# design.net
KiCad netlist of a schematic drawn in Altium Designer
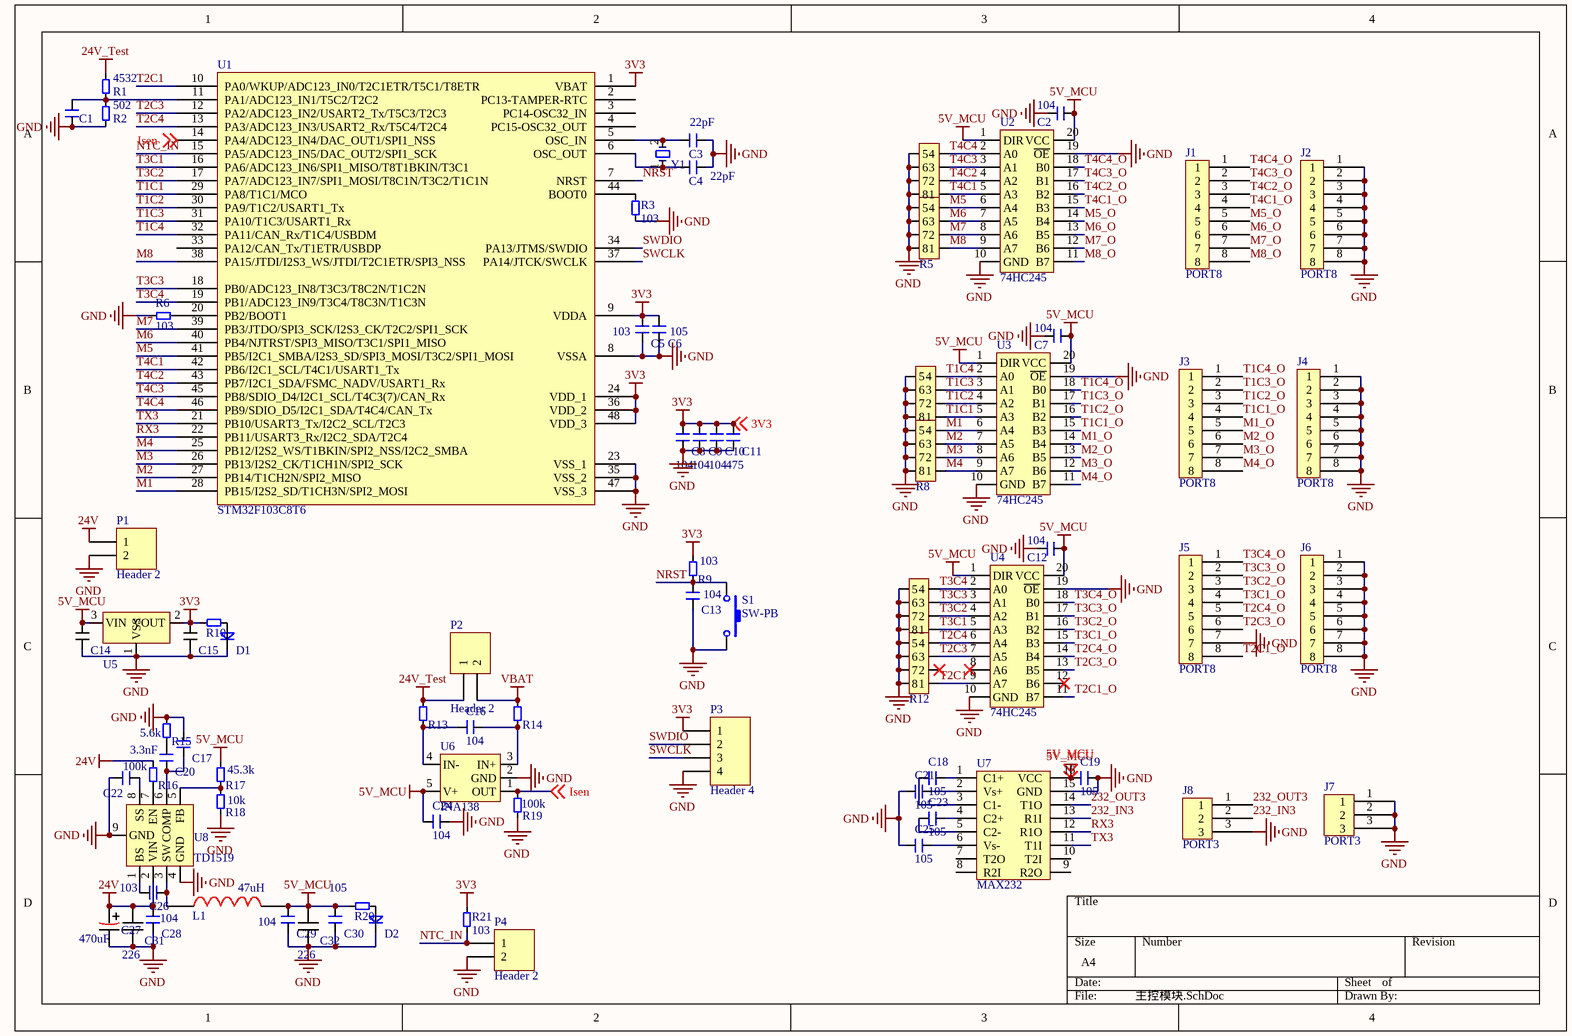
[diagram p0: 主控模块.SchDoc]

(export (version "E")
  (design (tool "Eeschema 10.0.6"))
  (components
    (comp (ref "C1") (value "0603C") (footprint "0603C") (libsource (lib "水下机器人电调控制板2020") (part "0603C")))
    (comp (ref "C2")
      (value "0603C")
      (footprint "0603C")
      (fields (field (name "PARAMETER 1") "104"))
      (libsource (lib "水下机器人电调控制板2020") (part "0603C"))
    )
    (comp (ref "C3")
      (value "0603C")
      (footprint "0603C")
      (fields (field (name "PARAMETER 1") "22pF"))
      (libsource (lib "水下机器人电调控制板2020") (part "0603C"))
    )
    (comp (ref "C4")
      (value "0603C")
      (footprint "0603C")
      (fields (field (name "PARAMETER 1") "22pF"))
      (libsource (lib "水下机器人电调控制板2020") (part "0603C"))
    )
    (comp (ref "C5")
      (value "0603C")
      (footprint "0603C")
      (fields (field (name "PARAMETER 1") "103"))
      (libsource (lib "水下机器人电调控制板2020") (part "0603C"))
    )
    (comp (ref "C6")
      (value "0603C")
      (footprint "0603C")
      (fields (field (name "PARAMETER 1") "105"))
      (libsource (lib "水下机器人电调控制板2020") (part "0603C"))
    )
    (comp (ref "C7")
      (value "0603C")
      (footprint "0603C")
      (fields (field (name "PARAMETER 1") "104"))
      (libsource (lib "水下机器人电调控制板2020") (part "0603C"))
    )
    (comp (ref "C8")
      (value "0603C")
      (footprint "0603C")
      (fields (field (name "PARAMETER 1") "104"))
      (libsource (lib "水下机器人电调控制板2020") (part "0603C"))
    )
    (comp (ref "C9")
      (value "0603C")
      (footprint "0603C")
      (fields (field (name "PARAMETER 1") "104"))
      (libsource (lib "水下机器人电调控制板2020") (part "0603C"))
    )
    (comp (ref "C10")
      (value "0603C")
      (footprint "0603C")
      (fields (field (name "PARAMETER 1") "104"))
      (libsource (lib "水下机器人电调控制板2020") (part "0603C"))
    )
    (comp (ref "C11")
      (value "0603C")
      (footprint "0603C")
      (fields (field (name "PARAMETER 1") "475"))
      (libsource (lib "水下机器人电调控制板2020") (part "0603C"))
    )
    (comp (ref "C12")
      (value "0603C")
      (footprint "0603C")
      (fields (field (name "PARAMETER 1") "104"))
      (libsource (lib "水下机器人电调控制板2020") (part "0603C"))
    )
    (comp (ref "C13")
      (value "0603C")
      (footprint "0603C")
      (fields (field (name "PARAMETER 1") "104"))
      (libsource (lib "水下机器人电调控制板2020") (part "0603C"))
    )
    (comp (ref "C14") (value "0805C") (footprint "0805C") (libsource (lib "水下去机器人控制板2020") (part "0805C")))
    (comp (ref "C15") (value "0805C") (footprint "0805C") (libsource (lib "水下去机器人控制板2020") (part "0805C")))
    (comp (ref "C16")
      (value "0603C")
      (footprint "0603C")
      (fields (field (name "PARAMETER 1") "104"))
      (libsource (lib "水下去机器人控制板2020") (part "0603C"))
    )
    (comp (ref "C17") (value "0603C") (footprint "0603C") (libsource (lib "水下去机器人控制板2020") (part "0603C")))
    (comp (ref "C18")
      (value "0603C")
      (footprint "0603C")
      (fields (field (name "PARAMETER 1") "105"))
      (libsource (lib "水下去机器人控制板2020") (part "0603C"))
    )
    (comp (ref "C19")
      (value "0603C")
      (footprint "0603C")
      (fields (field (name "PARAMETER 1") "105"))
      (libsource (lib "水下去机器人控制板2020") (part "0603C"))
    )
    (comp (ref "C20")
      (value "0603C")
      (footprint "0603C")
      (fields (field (name "PARAMETER 1") "3.3nF"))
      (libsource (lib "水下去机器人控制板2020") (part "0603C"))
    )
    (comp (ref "C21")
      (value "0603C")
      (footprint "0603C")
      (fields (field (name "PARAMETER 1") "105"))
      (libsource (lib "水下去机器人控制板2020") (part "0603C"))
    )
    (comp (ref "C22") (value "0603C") (footprint "0603C") (libsource (lib "水下去机器人控制板2020") (part "0603C")))
    (comp (ref "C23")
      (value "0603C")
      (footprint "0603C")
      (fields (field (name "PARAMETER 1") "105"))
      (libsource (lib "水下去机器人控制板2020") (part "0603C"))
    )
    (comp (ref "C24")
      (value "0603C")
      (footprint "0603C")
      (fields (field (name "PARAMETER 1") "104"))
      (libsource (lib "水下去机器人控制板2020") (part "0603C"))
    )
    (comp (ref "C25")
      (value "0603C")
      (footprint "0603C")
      (fields (field (name "PARAMETER 1") "105"))
      (libsource (lib "水下去机器人控制板2020") (part "0603C"))
    )
    (comp (ref "C26")
      (value "0603C")
      (footprint "0603C")
      (fields (field (name "PARAMETER 1") "103"))
      (libsource (lib "水下去机器人控制板2020") (part "0603C"))
    )
    (comp (ref "C27")
      (value "10*10贴片电解电容")
      (footprint "CAP-10*10.2")
      (fields (field (name "PARAMETER 1") "470uF"))
      (libsource (lib "水下去机器人控制板2020") (part "10*10贴片电解电容"))
    )
    (comp (ref "C28")
      (value "0603C")
      (footprint "0603C")
      (fields (field (name "PARAMETER 1") "104"))
      (libsource (lib "水下去机器人控制板2020") (part "0603C"))
    )
    (comp (ref "C29")
      (value "0603C")
      (footprint "0603C")
      (fields (field (name "PARAMETER 1") "104"))
      (libsource (lib "水下去机器人控制板2020") (part "0603C"))
    )
    (comp (ref "C30")
      (value "0603C")
      (footprint "0603C")
      (fields (field (name "PARAMETER 1") "105"))
      (libsource (lib "水下去机器人控制板2020") (part "0603C"))
    )
    (comp (ref "C31")
      (value "1206C")
      (footprint "1206C")
      (fields (field (name "PARAMETER 1") "226"))
      (libsource (lib "") (part "1206C_1"))
    )
    (comp (ref "C32")
      (value "1206C")
      (footprint "固态电容5*9")
      (fields (field (name "PARAMETER 1") "226"))
      (libsource (lib "水下去机器人控制板2020") (part "1206C"))
    )
    (comp (ref "D1") (value "0603D") (footprint "0603D") (libsource (lib "水下去机器人控制板2020") (part "0603D")))
    (comp (ref "D2") (value "0603D") (footprint "0603D") (libsource (lib "水下去机器人控制板2020") (part "0603D")))
    (comp (ref "J1") (value "PORT8") (footprint "PORT8") (libsource (lib "水下机器人电调控制板2020") (part "PORT8")))
    (comp (ref "J2") (value "PORT8") (footprint "PORT8") (libsource (lib "水下机器人电调控制板2020") (part "PORT8")))
    (comp (ref "J3") (value "PORT8") (footprint "PORT8") (libsource (lib "水下机器人电调控制板2020") (part "PORT8")))
    (comp (ref "J4") (value "PORT8") (footprint "PORT8") (libsource (lib "水下机器人电调控制板2020") (part "PORT8")))
    (comp (ref "J5") (value "PORT8") (footprint "PORT8") (libsource (lib "水下机器人电调控制板2020") (part "PORT8")))
    (comp (ref "J6") (value "PORT8") (footprint "PORT8") (libsource (lib "水下机器人电调控制板2020") (part "PORT8")))
    (comp (ref "J7") (value "PORT3") (footprint "PORT3") (libsource (lib "水下机器人电调控制板2020") (part "PORT3")))
    (comp (ref "J8") (value "PORT3") (footprint "PORT3") (libsource (lib "水下机器人电调控制板2020") (part "PORT3")))
    (comp (ref "L1")
      (value "1265L")
      (footprint "1265L")
      (fields (field (name "PARAMETER 1") "47uH"))
      (libsource (lib "水下去机器人控制板2020") (part "1265L"))
    )
    (comp (ref "P1")
      (value "Header 2")
      (footprint "DB129-2")
      (description "Header, 2-Pin")
      (fields (field (name "PUBLISHER") "Altium Limited"))
      (libsource (lib "Miscellaneous Connectors") (part "Header 2"))
    )
    (comp (ref "P2")
      (value "Header 2")
      (footprint "HDR1X2")
      (description "Header, 2-Pin")
      (fields (field (name "PUBLISHER") "Altium Limited"))
      (libsource (lib "") (part "Header 2_1"))
    )
    (comp (ref "P3")
      (value "Header 4")
      (footprint "HDR1X4")
      (description "Header, 4-Pin")
      (fields (field (name "PUBLISHER") "Altium Limited"))
      (libsource (lib "Miscellaneous Connectors") (part "Header 4"))
    )
    (comp (ref "P4")
      (value "Header 2")
      (footprint "HDR1X2")
      (description "Header, 2-Pin")
      (fields (field (name "PUBLISHER") "Altium Limited"))
      (libsource (lib "Miscellaneous Connectors") (part "Header 2"))
    )
    (comp (ref "R1") (value "4532") (footprint "0603R") (libsource (lib "水下机器人电调控制板2020") (part "0603R")))
    (comp (ref "R2") (value "502") (footprint "0603R") (libsource (lib "水下机器人电调控制板2020") (part "0603R")))
    (comp (ref "R3")
      (value "0603R")
      (footprint "0603R")
      (fields (field (name "PARAMETER 1") "103"))
      (libsource (lib "水下机器人电调控制板2020") (part "0603R"))
    )
    (comp (ref "R4") (value "排阻") (footprint "0603RA") (libsource (lib "SC8815带控制显示") (part "排阻")))
    (comp (ref "R5") (value "排阻") (footprint "0603RA") (libsource (lib "SC8815带控制显示") (part "排阻")))
    (comp (ref "R6")
      (value "0603R")
      (footprint "0603R")
      (fields (field (name "PARAMETER 1") "103"))
      (libsource (lib "水下机器人电调控制板2020") (part "0603R"))
    )
    (comp (ref "R7") (value "排阻") (footprint "0603RA") (libsource (lib "SC8815带控制显示") (part "排阻")))
    (comp (ref "R8") (value "排阻") (footprint "0603RA") (libsource (lib "SC8815带控制显示") (part "排阻")))
    (comp (ref "R9")
      (value "0603R")
      (footprint "0603R")
      (fields (field (name "PARAMETER 1") "103"))
      (libsource (lib "水下机器人电调控制板2020") (part "0603R"))
    )
    (comp (ref "R10") (value "0603R") (footprint "0603R") (libsource (lib "水下去机器人控制板2020") (part "0603R")))
    (comp (ref "R11") (value "排阻") (footprint "0603RA") (libsource (lib "SC8815带控制显示") (part "排阻")))
    (comp (ref "R12") (value "排阻") (footprint "0603RA") (libsource (lib "SC8815带控制显示") (part "排阻")))
    (comp (ref "R13") (value "0603R") (footprint "0603R") (libsource (lib "水下去机器人控制板2020") (part "0603R")))
    (comp (ref "R14") (value "0603R") (footprint "0603R") (libsource (lib "水下去机器人控制板2020") (part "0603R")))
    (comp (ref "R15")
      (value "0603R")
      (footprint "0603R")
      (fields (field (name "PARAMETER 1") "5.6k"))
      (libsource (lib "水下去机器人控制板2020") (part "0603R"))
    )
    (comp (ref "R16")
      (value "0603R")
      (footprint "0603R")
      (fields (field (name "PARAMETER 1") "100k"))
      (libsource (lib "水下去机器人控制板2020") (part "0603R"))
    )
    (comp (ref "R17")
      (value "0603R")
      (footprint "0603R")
      (fields (field (name "PARAMETER 1") "45.3k"))
      (libsource (lib "水下去机器人控制板2020") (part "0603R"))
    )
    (comp (ref "R18")
      (value "0603R")
      (footprint "0603R")
      (fields (field (name "PARAMETER 1") "10k"))
      (libsource (lib "水下去机器人控制板2020") (part "0603R"))
    )
    (comp (ref "R19")
      (value "0603R")
      (footprint "0603R")
      (fields (field (name "PARAMETER 1") "100k"))
      (libsource (lib "水下去机器人控制板2020") (part "0603R"))
    )
    (comp (ref "R20") (value "0603R") (footprint "0603R") (libsource (lib "水下去机器人控制板2020") (part "0603R")))
    (comp (ref "R21")
      (value "0603R")
      (footprint "0603R")
      (fields (field (name "PARAMETER 1") "103"))
      (libsource (lib "水下去机器人控制板2020") (part "0603R"))
    )
    (comp (ref "S1")
      (value "SW-PB")
      (footprint "按键 3x6")
      (description "Switch")
      (fields (field (name "PUBLISHER") "Altium Limited"))
      (libsource (lib "Miscellaneous Devices") (part "SW-PB"))
    )
    (comp (ref "U1")
      (value "STM32F103C8T6")
      (footprint "QFP48")
      (libsource (lib "水下机器人电调控制板2020") (part "STM32F103C8T6"))
    )
    (comp (ref "U2")
      (value "74HC245")
      (footprint "TSSOP20-OR65-4R40")
      (libsource (lib "水下机器人电调控制板2020") (part "74HC245"))
    )
    (comp (ref "U3")
      (value "74HC245")
      (footprint "TSSOP20-OR65-4R40")
      (libsource (lib "水下机器人电调控制板2020") (part "74HC245"))
    )
    (comp (ref "U4")
      (value "74HC245")
      (footprint "TSSOP20-OR65-4R40")
      (libsource (lib "水下机器人电调控制板2020") (part "74HC245"))
    )
    (comp (ref "U5") (value "662k") (footprint "SOT23-3") (libsource (lib "水下去机器人控制板2020") (part "662k")))
    (comp (ref "U6")
      (value "INA138")
      (footprint "SOT23-5")
      (libsource (lib "水下机器人电调控制板2020") (part "INA138"))
    )
    (comp (ref "U7") (value "MAX232") (footprint "SOP16") (libsource (lib "CH340转232") (part "MAX232")))
    (comp (ref "U8")
      (value "TD1519")
      (footprint "SOP8-PAD")
      (libsource (lib "水下去机器人控制板2020") (part "TD1519"))
    )
    (comp (ref "Y1")
      (value "XTAL_5032")
      (footprint "XTAL贴片")
      (libsource (lib "水下机器人电调控制板2020") (part "XTAL_5032"))
    )
  )
  (nets
    (net (code "1") (name "/232_IN3") (class "Default")
      (node (ref "J8") (pin "2") (pinfunction "2_2") (pintype "passive"))
      (node (ref "U7") (pin "13") (pinfunction "R1I_13") (pintype "passive"))
    )
    (net (code "2") (name "/232_OUT3") (class "Default")
      (node (ref "J8") (pin "1") (pinfunction "1_1") (pintype "passive"))
      (node (ref "U7") (pin "14") (pinfunction "T1O_14") (pintype "passive"))
    )
    (net (code "3") (name "/M1") (class "Default")
      (node (ref "R8") (pin "4") (pinfunction "4_4") (pintype "passive"))
      (node (ref "U1") (pin "28") (pinfunction "PB15/I2S2_SD/T1CH3N/SPI2_MOSI_28") (pintype "passive"))
      (node (ref "U3") (pin "6") (pinfunction "A4_6") (pintype "passive"))
    )
    (net (code "4") (name "/M1_O") (class "Default")
      (node (ref "J3") (pin "5") (pinfunction "5_5") (pintype "passive"))
      (node (ref "U3") (pin "14") (pinfunction "B4_14") (pintype "passive"))
    )
    (net (code "5") (name "/M2") (class "Default")
      (node (ref "R8") (pin "3") (pinfunction "3_3") (pintype "passive"))
      (node (ref "U1") (pin "27") (pinfunction "PB14/T1CH2N/SPI2_MISO_27") (pintype "passive"))
      (node (ref "U3") (pin "7") (pinfunction "A5_7") (pintype "passive"))
    )
    (net (code "6") (name "/M2_O") (class "Default")
      (node (ref "J3") (pin "6") (pinfunction "6_6") (pintype "passive"))
      (node (ref "U3") (pin "13") (pinfunction "B5_13") (pintype "passive"))
    )
    (net (code "7") (name "/M3") (class "Default")
      (node (ref "R8") (pin "2") (pinfunction "2_2") (pintype "passive"))
      (node (ref "U1") (pin "26") (pinfunction "PB13/I2S2_CK/T1CH1N/SPI2_SCK_26") (pintype "passive"))
      (node (ref "U3") (pin "8") (pinfunction "A6_8") (pintype "passive"))
    )
    (net (code "8") (name "/M3_O") (class "Default")
      (node (ref "J3") (pin "7") (pinfunction "7_7") (pintype "passive"))
      (node (ref "U3") (pin "12") (pinfunction "B6_12") (pintype "passive"))
    )
    (net (code "9") (name "/M4") (class "Default")
      (node (ref "R8") (pin "1") (pinfunction "1_1") (pintype "passive"))
      (node (ref "U1") (pin "25") (pinfunction "PB12/I2S2_WS/T1BKIN/SPI2_NSS/I2C2_SMBA_25") (pintype "passive"))
      (node (ref "U3") (pin "9") (pinfunction "A7_9") (pintype "passive"))
    )
    (net (code "10") (name "/M4_O") (class "Default")
      (node (ref "J3") (pin "8") (pinfunction "8_8") (pintype "passive"))
      (node (ref "U3") (pin "11") (pinfunction "B7_11") (pintype "passive"))
    )
    (net (code "11") (name "/M5") (class "Default")
      (node (ref "R5") (pin "4") (pinfunction "4_4") (pintype "passive"))
      (node (ref "U1") (pin "41") (pinfunction "PB5/I2C1_SMBA/I2S3_SD/SPI3_MOSI/T3C2/SPI1_MOSI_41") (pintype "passive"))
      (node (ref "U2") (pin "6") (pinfunction "A4_6") (pintype "passive"))
    )
    (net (code "12") (name "/M5_O") (class "Default")
      (node (ref "J1") (pin "5") (pinfunction "5_5") (pintype "passive"))
      (node (ref "U2") (pin "14") (pinfunction "B4_14") (pintype "passive"))
    )
    (net (code "13") (name "/M6") (class "Default")
      (node (ref "R5") (pin "3") (pinfunction "3_3") (pintype "passive"))
      (node (ref "U1") (pin "40") (pinfunction "PB4/NJTRST/SPI3_MISO/T3C1/SPI1_MISO_40") (pintype "passive"))
      (node (ref "U2") (pin "7") (pinfunction "A5_7") (pintype "passive"))
    )
    (net (code "14") (name "/M6_O") (class "Default")
      (node (ref "J1") (pin "6") (pinfunction "6_6") (pintype "passive"))
      (node (ref "U2") (pin "13") (pinfunction "B5_13") (pintype "passive"))
    )
    (net (code "15") (name "/M7") (class "Default")
      (node (ref "R5") (pin "2") (pinfunction "2_2") (pintype "passive"))
      (node (ref "U1") (pin "39") (pinfunction "PB3/JTDO/SPI3_SCK/I2S3_CK/T2C2/SPI1_SCK_39") (pintype "passive"))
      (node (ref "U2") (pin "8") (pinfunction "A6_8") (pintype "passive"))
    )
    (net (code "16") (name "/M7_O") (class "Default")
      (node (ref "J1") (pin "7") (pinfunction "7_7") (pintype "passive"))
      (node (ref "U2") (pin "12") (pinfunction "B6_12") (pintype "passive"))
    )
    (net (code "17") (name "/M8") (class "Default")
      (node (ref "R5") (pin "1") (pinfunction "1_1") (pintype "passive"))
      (node (ref "U1") (pin "38") (pinfunction "PA15/JTDI/I2S3_WS/JTDI/T2C1ETR/SPI3_NSS_38") (pintype "passive"))
      (node (ref "U2") (pin "9") (pinfunction "A7_9") (pintype "passive"))
    )
    (net (code "18") (name "/M8_O") (class "Default")
      (node (ref "J1") (pin "8") (pinfunction "8_8") (pintype "passive"))
      (node (ref "U2") (pin "11") (pinfunction "B7_11") (pintype "passive"))
    )
    (net (code "19") (name "/NRST") (class "Default")
      (node (ref "C13") (pin "2") (pinfunction "2_2") (pintype "passive"))
      (node (ref "R9") (pin "1") (pinfunction "1_1") (pintype "passive"))
      (node (ref "S1") (pin "1") (pinfunction "1_1") (pintype "passive"))
      (node (ref "U1") (pin "7") (pinfunction "NRST_7") (pintype "passive"))
    )
    (net (code "20") (name "/NTC_IN") (class "Default")
      (node (ref "P4") (pin "1") (pinfunction "1_1") (pintype "passive"))
      (node (ref "R21") (pin "1") (pinfunction "1_1") (pintype "passive"))
      (node (ref "U1") (pin "15") (pinfunction "PA5/ADC123_IN5/DAC_OUT2/SPI1_SCK_15") (pintype "passive"))
    )
    (net (code "21") (name "/RX3") (class "Default")
      (node (ref "U1") (pin "22") (pinfunction "PB11/USART3_Rx/I2C2_SDA/T2C4_22") (pintype "passive"))
      (node (ref "U7") (pin "12") (pinfunction "R1O_12") (pintype "passive"))
    )
    (net (code "22") (name "/SWCLK") (class "Default")
      (node (ref "P3") (pin "3") (pinfunction "3_3") (pintype "passive"))
      (node (ref "U1") (pin "37") (pinfunction "PA14/JTCK/SWCLK_37") (pintype "passive"))
    )
    (net (code "23") (name "/SWDIO") (class "Default")
      (node (ref "P3") (pin "2") (pinfunction "2_2") (pintype "passive"))
      (node (ref "U1") (pin "34") (pinfunction "PA13/JTMS/SWDIO_34") (pintype "passive"))
    )
    (net (code "24") (name "/T1C1") (class "Default")
      (node (ref "R7") (pin "1") (pinfunction "1_1") (pintype "passive"))
      (node (ref "U1") (pin "29") (pinfunction "PA8/T1C1/MCO_29") (pintype "passive"))
      (node (ref "U3") (pin "5") (pinfunction "A3_5") (pintype "passive"))
    )
    (net (code "25") (name "/T1C1_O") (class "Default")
      (node (ref "J3") (pin "4") (pinfunction "4_4") (pintype "passive"))
      (node (ref "U3") (pin "15") (pinfunction "B3_15") (pintype "passive"))
    )
    (net (code "26") (name "/T1C2") (class "Default")
      (node (ref "R7") (pin "2") (pinfunction "2_2") (pintype "passive"))
      (node (ref "U1") (pin "30") (pinfunction "PA9/T1C2/USART1_Tx_30") (pintype "passive"))
      (node (ref "U3") (pin "4") (pinfunction "A2_4") (pintype "passive"))
    )
    (net (code "27") (name "/T1C2_O") (class "Default")
      (node (ref "J3") (pin "3") (pinfunction "3_3") (pintype "passive"))
      (node (ref "U3") (pin "16") (pinfunction "B2_16") (pintype "passive"))
    )
    (net (code "28") (name "/T1C3") (class "Default")
      (node (ref "R7") (pin "3") (pinfunction "3_3") (pintype "passive"))
      (node (ref "U1") (pin "31") (pinfunction "PA10/T1C3/USART1_Rx_31") (pintype "passive"))
      (node (ref "U3") (pin "3") (pinfunction "A1_3") (pintype "passive"))
    )
    (net (code "29") (name "/T1C3_O") (class "Default")
      (node (ref "J3") (pin "2") (pinfunction "2_2") (pintype "passive"))
      (node (ref "U3") (pin "17") (pinfunction "B1_17") (pintype "passive"))
    )
    (net (code "30") (name "/T1C4") (class "Default")
      (node (ref "R7") (pin "4") (pinfunction "4_4") (pintype "passive"))
      (node (ref "U1") (pin "32") (pinfunction "PA11/CAN_Rx/T1C4/USBDM_32") (pintype "passive"))
      (node (ref "U3") (pin "2") (pinfunction "A0_2") (pintype "passive"))
    )
    (net (code "31") (name "/T1C4_O") (class "Default")
      (node (ref "J3") (pin "1") (pinfunction "1_1") (pintype "passive"))
      (node (ref "U3") (pin "18") (pinfunction "B0_18") (pintype "passive"))
    )
    (net (code "32") (name "/T2C1") (class "Default")
      (node (ref "R12") (pin "1") (pinfunction "1_1") (pintype "passive"))
      (node (ref "U1") (pin "10") (pinfunction "PA0/WKUP/ADC123_IN0/T2C1ETR/T5C1/T8ETR_10") (pintype "passive"))
      (node (ref "U4") (pin "9") (pinfunction "A7_9") (pintype "passive"))
    )
    (net (code "33") (name "/T2C1_O") (class "Default")
      (node (ref "J5") (pin "8") (pinfunction "8_8") (pintype "passive"))
      (node (ref "U4") (pin "11") (pinfunction "B7_11") (pintype "passive"))
    )
    (net (code "34") (name "/T2C3") (class "Default")
      (node (ref "R12") (pin "3") (pinfunction "3_3") (pintype "passive"))
      (node (ref "U1") (pin "12") (pinfunction "PA2/ADC123_IN2/USART2_Tx/T5C3/T2C3_12") (pintype "passive"))
      (node (ref "U4") (pin "7") (pinfunction "A5_7") (pintype "passive"))
    )
    (net (code "35") (name "/T2C3_O") (class "Default")
      (node (ref "J5") (pin "6") (pinfunction "6_6") (pintype "passive"))
      (node (ref "U4") (pin "13") (pinfunction "B5_13") (pintype "passive"))
    )
    (net (code "36") (name "/T2C4") (class "Default")
      (node (ref "R12") (pin "4") (pinfunction "4_4") (pintype "passive"))
      (node (ref "U1") (pin "13") (pinfunction "PA3/ADC123_IN3/USART2_Rx/T5C4/T2C4_13") (pintype "passive"))
      (node (ref "U4") (pin "6") (pinfunction "A4_6") (pintype "passive"))
    )
    (net (code "37") (name "/T2C4_O") (class "Default")
      (node (ref "J5") (pin "5") (pinfunction "5_5") (pintype "passive"))
      (node (ref "U4") (pin "14") (pinfunction "B4_14") (pintype "passive"))
    )
    (net (code "38") (name "/T3C1") (class "Default")
      (node (ref "R11") (pin "1") (pinfunction "1_1") (pintype "passive"))
      (node (ref "U1") (pin "16") (pinfunction "PA6/ADC123_IN6/SPI1_MISO/T8T1BKIN/T3C1_16") (pintype "passive"))
      (node (ref "U4") (pin "5") (pinfunction "A3_5") (pintype "passive"))
    )
    (net (code "39") (name "/T3C1_O") (class "Default")
      (node (ref "J5") (pin "4") (pinfunction "4_4") (pintype "passive"))
      (node (ref "U4") (pin "15") (pinfunction "B3_15") (pintype "passive"))
    )
    (net (code "40") (name "/T3C2") (class "Default")
      (node (ref "R11") (pin "2") (pinfunction "2_2") (pintype "passive"))
      (node (ref "U1") (pin "17") (pinfunction "PA7/ADC123_IN7/SPI1_MOSI/T8C1N/T3C2/T1C1N_17") (pintype "passive"))
      (node (ref "U4") (pin "4") (pinfunction "A2_4") (pintype "passive"))
    )
    (net (code "41") (name "/T3C2_O") (class "Default")
      (node (ref "J5") (pin "3") (pinfunction "3_3") (pintype "passive"))
      (node (ref "U4") (pin "16") (pinfunction "B2_16") (pintype "passive"))
    )
    (net (code "42") (name "/T3C3") (class "Default")
      (node (ref "R11") (pin "3") (pinfunction "3_3") (pintype "passive"))
      (node (ref "U1") (pin "18") (pinfunction "PB0/ADC123_IN8/T3C3/T8C2N/T1C2N_18") (pintype "passive"))
      (node (ref "U4") (pin "3") (pinfunction "A1_3") (pintype "passive"))
    )
    (net (code "43") (name "/T3C3_O") (class "Default")
      (node (ref "J5") (pin "2") (pinfunction "2_2") (pintype "passive"))
      (node (ref "U4") (pin "17") (pinfunction "B1_17") (pintype "passive"))
    )
    (net (code "44") (name "/T3C4") (class "Default")
      (node (ref "R11") (pin "4") (pinfunction "4_4") (pintype "passive"))
      (node (ref "U1") (pin "19") (pinfunction "PB1/ADC123_IN9/T3C4/T8C3N/T1C3N_19") (pintype "passive"))
      (node (ref "U4") (pin "2") (pinfunction "A0_2") (pintype "passive"))
    )
    (net (code "45") (name "/T3C4_O") (class "Default")
      (node (ref "J5") (pin "1") (pinfunction "1_1") (pintype "passive"))
      (node (ref "U4") (pin "18") (pinfunction "B0_18") (pintype "passive"))
    )
    (net (code "46") (name "/T4C1") (class "Default")
      (node (ref "R4") (pin "1") (pinfunction "1_1") (pintype "passive"))
      (node (ref "U1") (pin "42") (pinfunction "PB6/I2C1_SCL/T4C1/USART1_Tx_42") (pintype "passive"))
      (node (ref "U2") (pin "5") (pinfunction "A3_5") (pintype "passive"))
    )
    (net (code "47") (name "/T4C1_O") (class "Default")
      (node (ref "J1") (pin "4") (pinfunction "4_4") (pintype "passive"))
      (node (ref "U2") (pin "15") (pinfunction "B3_15") (pintype "passive"))
    )
    (net (code "48") (name "/T4C2") (class "Default")
      (node (ref "R4") (pin "2") (pinfunction "2_2") (pintype "passive"))
      (node (ref "U1") (pin "43") (pinfunction "PB7/I2C1_SDA/FSMC_NADV/USART1_Rx_43") (pintype "passive"))
      (node (ref "U2") (pin "4") (pinfunction "A2_4") (pintype "passive"))
    )
    (net (code "49") (name "/T4C2_O") (class "Default")
      (node (ref "J1") (pin "3") (pinfunction "3_3") (pintype "passive"))
      (node (ref "U2") (pin "16") (pinfunction "B2_16") (pintype "passive"))
    )
    (net (code "50") (name "/T4C3") (class "Default")
      (node (ref "R4") (pin "3") (pinfunction "3_3") (pintype "passive"))
      (node (ref "U1") (pin "45") (pinfunction "PB8/SDIO_D4/I2C1_SCL/T4C3(7)/CAN_Rx_45") (pintype "passive"))
      (node (ref "U2") (pin "3") (pinfunction "A1_3") (pintype "passive"))
    )
    (net (code "51") (name "/T4C3_O") (class "Default")
      (node (ref "J1") (pin "2") (pinfunction "2_2") (pintype "passive"))
      (node (ref "U2") (pin "17") (pinfunction "B1_17") (pintype "passive"))
    )
    (net (code "52") (name "/T4C4") (class "Default")
      (node (ref "R4") (pin "4") (pinfunction "4_4") (pintype "passive"))
      (node (ref "U1") (pin "46") (pinfunction "PB9/SDIO_D5/I2C1_SDA/T4C4/CAN_Tx_46") (pintype "passive"))
      (node (ref "U2") (pin "2") (pinfunction "A0_2") (pintype "passive"))
    )
    (net (code "53") (name "/T4C4_O") (class "Default")
      (node (ref "J1") (pin "1") (pinfunction "1_1") (pintype "passive"))
      (node (ref "U2") (pin "18") (pinfunction "B0_18") (pintype "passive"))
    )
    (net (code "54") (name "/TX3") (class "Default")
      (node (ref "U1") (pin "21") (pinfunction "PB10/USART3_Tx/I2C2_SCL/T2C3_21") (pintype "passive"))
      (node (ref "U7") (pin "11") (pinfunction "T1I_11") (pintype "passive"))
    )
    (net (code "55") (name "3V3") (class "Default")
      (node (ref "C10") (pin "1") (pinfunction "1_1") (pintype "passive"))
      (node (ref "C11") (pin "1") (pinfunction "1_1") (pintype "passive"))
      (node (ref "C15") (pin "2") (pinfunction "2_2") (pintype "passive"))
      (node (ref "C5") (pin "2") (pinfunction "2_2") (pintype "passive"))
      (node (ref "C6") (pin "2") (pinfunction "2_2") (pintype "passive"))
      (node (ref "C8") (pin "1") (pinfunction "1_1") (pintype "passive"))
      (node (ref "C9") (pin "1") (pinfunction "1_1") (pintype "passive"))
      (node (ref "P3") (pin "1") (pinfunction "1_1") (pintype "passive"))
      (node (ref "R10") (pin "1") (pinfunction "1_1") (pintype "passive"))
      (node (ref "R21") (pin "2") (pinfunction "2_2") (pintype "passive"))
      (node (ref "R9") (pin "2") (pinfunction "2_2") (pintype "passive"))
      (node (ref "U1") (pin "1") (pinfunction "VBAT_1") (pintype "passive"))
      (node (ref "U1") (pin "24") (pinfunction "VDD_1_24") (pintype "passive"))
      (node (ref "U1") (pin "36") (pinfunction "VDD_2_36") (pintype "passive"))
      (node (ref "U1") (pin "48") (pinfunction "VDD_3_48") (pintype "passive"))
      (node (ref "U1") (pin "9") (pinfunction "VDDA_9") (pintype "passive"))
      (node (ref "U5") (pin "2") (pinfunction "VOUT_2") (pintype "passive"))
    )
    (net (code "56") (name "5V_MCU") (class "Default")
      (node (ref "C12") (pin "2") (pinfunction "2_2") (pintype "passive"))
      (node (ref "C14") (pin "2") (pinfunction "2_2") (pintype "passive"))
      (node (ref "C19") (pin "1") (pinfunction "1_1") (pintype "passive"))
      (node (ref "C2") (pin "2") (pinfunction "2_2") (pintype "passive"))
      (node (ref "C24") (pin "2") (pinfunction "2_2") (pintype "passive"))
      (node (ref "C29") (pin "2") (pinfunction "2_2") (pintype "passive"))
      (node (ref "C30") (pin "2") (pinfunction "2_2") (pintype "passive"))
      (node (ref "C32") (pin "2") (pinfunction "2_2") (pintype "passive"))
      (node (ref "C7") (pin "2") (pinfunction "2_2") (pintype "passive"))
      (node (ref "L1") (pin "2") (pinfunction "2_2") (pintype "passive"))
      (node (ref "R17") (pin "2") (pinfunction "2_2") (pintype "passive"))
      (node (ref "R20") (pin "1") (pinfunction "1_1") (pintype "passive"))
      (node (ref "U2") (pin "1") (pinfunction "DIR_1") (pintype "passive"))
      (node (ref "U2") (pin "20") (pinfunction "VCC_20") (pintype "passive"))
      (node (ref "U3") (pin "1") (pinfunction "DIR_1") (pintype "passive"))
      (node (ref "U3") (pin "20") (pinfunction "VCC_20") (pintype "passive"))
      (node (ref "U4") (pin "1") (pinfunction "DIR_1") (pintype "passive"))
      (node (ref "U4") (pin "20") (pinfunction "VCC_20") (pintype "passive"))
      (node (ref "U5") (pin "3") (pinfunction "VIN_3") (pintype "passive"))
      (node (ref "U6") (pin "5") (pinfunction "V+_5") (pintype "power_in"))
      (node (ref "U7") (pin "16") (pinfunction "VCC_16") (pintype "passive"))
    )
    (net (code "57") (name "24V") (class "Default")
      (node (ref "C27") (pin "1") (pinfunction "1_1") (pintype "passive"))
      (node (ref "C28") (pin "2") (pinfunction "2_2") (pintype "passive"))
      (node (ref "C31") (pin "1") (pinfunction "1_1") (pintype "passive"))
      (node (ref "P1") (pin "1") (pinfunction "1_1") (pintype "passive"))
      (node (ref "R16") (pin "2") (pinfunction "2_2") (pintype "passive"))
      (node (ref "U8") (pin "2") (pinfunction "VIN_2") (pintype "power_in"))
    )
    (net (code "58") (name "24V_Test") (class "Default")
      (node (ref "P2") (pin "1") (pinfunction "1_1") (pintype "passive"))
      (node (ref "R1") (pin "1") (pinfunction "1_1") (pintype "passive"))
      (node (ref "R13") (pin "2") (pinfunction "2_2") (pintype "passive"))
    )
    (net (code "59") (name "GND") (class "Default")
      (node (ref "C1") (pin "1") (pinfunction "1_1") (pintype "passive"))
      (node (ref "C10") (pin "2") (pinfunction "2_2") (pintype "passive"))
      (node (ref "C11") (pin "2") (pinfunction "2_2") (pintype "passive"))
      (node (ref "C12") (pin "1") (pinfunction "1_1") (pintype "passive"))
      (node (ref "C13") (pin "1") (pinfunction "1_1") (pintype "passive"))
      (node (ref "C14") (pin "1") (pinfunction "1_1") (pintype "passive"))
      (node (ref "C15") (pin "1") (pinfunction "1_1") (pintype "passive"))
      (node (ref "C17") (pin "1") (pinfunction "1_1") (pintype "passive"))
      (node (ref "C19") (pin "2") (pinfunction "2_2") (pintype "passive"))
      (node (ref "C2") (pin "1") (pinfunction "1_1") (pintype "passive"))
      (node (ref "C21") (pin "1") (pinfunction "1_1") (pintype "passive"))
      (node (ref "C22") (pin "2") (pinfunction "2_2") (pintype "passive"))
      (node (ref "C24") (pin "1") (pinfunction "1_1") (pintype "passive"))
      (node (ref "C25") (pin "1") (pinfunction "1_1") (pintype "passive"))
      (node (ref "C27") (pin "2") (pinfunction "2_2") (pintype "passive"))
      (node (ref "C28") (pin "1") (pinfunction "1_1") (pintype "passive"))
      (node (ref "C29") (pin "1") (pinfunction "1_1") (pintype "passive"))
      (node (ref "C3") (pin "2") (pinfunction "2_2") (pintype "passive"))
      (node (ref "C30") (pin "1") (pinfunction "1_1") (pintype "passive"))
      (node (ref "C31") (pin "2") (pinfunction "2_2") (pintype "passive"))
      (node (ref "C32") (pin "1") (pinfunction "1_1") (pintype "passive"))
      (node (ref "C4") (pin "2") (pinfunction "2_2") (pintype "passive"))
      (node (ref "C5") (pin "1") (pinfunction "1_1") (pintype "passive"))
      (node (ref "C6") (pin "1") (pinfunction "1_1") (pintype "passive"))
      (node (ref "C7") (pin "1") (pinfunction "1_1") (pintype "passive"))
      (node (ref "C8") (pin "2") (pinfunction "2_2") (pintype "passive"))
      (node (ref "C9") (pin "2") (pinfunction "2_2") (pintype "passive"))
      (node (ref "D1") (pin "2") (pinfunction "2_2") (pintype "passive"))
      (node (ref "D2") (pin "2") (pinfunction "2_2") (pintype "passive"))
      (node (ref "J2") (pin "1") (pinfunction "1_1") (pintype "passive"))
      (node (ref "J2") (pin "2") (pinfunction "2_2") (pintype "passive"))
      (node (ref "J2") (pin "3") (pinfunction "3_3") (pintype "passive"))
      (node (ref "J2") (pin "4") (pinfunction "4_4") (pintype "passive"))
      (node (ref "J2") (pin "5") (pinfunction "5_5") (pintype "passive"))
      (node (ref "J2") (pin "6") (pinfunction "6_6") (pintype "passive"))
      (node (ref "J2") (pin "7") (pinfunction "7_7") (pintype "passive"))
      (node (ref "J2") (pin "8") (pinfunction "8_8") (pintype "passive"))
      (node (ref "J4") (pin "1") (pinfunction "1_1") (pintype "passive"))
      (node (ref "J4") (pin "2") (pinfunction "2_2") (pintype "passive"))
      (node (ref "J4") (pin "3") (pinfunction "3_3") (pintype "passive"))
      (node (ref "J4") (pin "4") (pinfunction "4_4") (pintype "passive"))
      (node (ref "J4") (pin "5") (pinfunction "5_5") (pintype "passive"))
      (node (ref "J4") (pin "6") (pinfunction "6_6") (pintype "passive"))
      (node (ref "J4") (pin "7") (pinfunction "7_7") (pintype "passive"))
      (node (ref "J4") (pin "8") (pinfunction "8_8") (pintype "passive"))
      (node (ref "J5") (pin "7") (pinfunction "7_7") (pintype "passive"))
      (node (ref "J6") (pin "1") (pinfunction "1_1") (pintype "passive"))
      (node (ref "J6") (pin "2") (pinfunction "2_2") (pintype "passive"))
      (node (ref "J6") (pin "3") (pinfunction "3_3") (pintype "passive"))
      (node (ref "J6") (pin "4") (pinfunction "4_4") (pintype "passive"))
      (node (ref "J6") (pin "5") (pinfunction "5_5") (pintype "passive"))
      (node (ref "J6") (pin "6") (pinfunction "6_6") (pintype "passive"))
      (node (ref "J6") (pin "7") (pinfunction "7_7") (pintype "passive"))
      (node (ref "J6") (pin "8") (pinfunction "8_8") (pintype "passive"))
      (node (ref "J7") (pin "1") (pinfunction "1_1") (pintype "passive"))
      (node (ref "J7") (pin "2") (pinfunction "2_2") (pintype "passive"))
      (node (ref "J7") (pin "3") (pinfunction "3_3") (pintype "passive"))
      (node (ref "J8") (pin "3") (pinfunction "3_3") (pintype "passive"))
      (node (ref "P1") (pin "2") (pinfunction "2_2") (pintype "passive"))
      (node (ref "P3") (pin "4") (pinfunction "4_4") (pintype "passive"))
      (node (ref "P4") (pin "2") (pinfunction "2_2") (pintype "passive"))
      (node (ref "R11") (pin "5") (pinfunction "5_5") (pintype "passive"))
      (node (ref "R11") (pin "6") (pinfunction "6_6") (pintype "passive"))
      (node (ref "R11") (pin "7") (pinfunction "7_7") (pintype "passive"))
      (node (ref "R11") (pin "8") (pinfunction "8_8") (pintype "passive"))
      (node (ref "R12") (pin "5") (pinfunction "5_5") (pintype "passive"))
      (node (ref "R12") (pin "6") (pinfunction "6_6") (pintype "passive"))
      (node (ref "R12") (pin "7") (pinfunction "7_7") (pintype "passive"))
      (node (ref "R12") (pin "8") (pinfunction "8_8") (pintype "passive"))
      (node (ref "R15") (pin "2") (pinfunction "2_2") (pintype "passive"))
      (node (ref "R18") (pin "1") (pinfunction "1_1") (pintype "passive"))
      (node (ref "R19") (pin "1") (pinfunction "1_1") (pintype "passive"))
      (node (ref "R2") (pin "2") (pinfunction "2_2") (pintype "passive"))
      (node (ref "R3") (pin "1") (pinfunction "1_1") (pintype "passive"))
      (node (ref "R4") (pin "5") (pinfunction "5_5") (pintype "passive"))
      (node (ref "R4") (pin "6") (pinfunction "6_6") (pintype "passive"))
      (node (ref "R4") (pin "7") (pinfunction "7_7") (pintype "passive"))
      (node (ref "R4") (pin "8") (pinfunction "8_8") (pintype "passive"))
      (node (ref "R5") (pin "5") (pinfunction "5_5") (pintype "passive"))
      (node (ref "R5") (pin "6") (pinfunction "6_6") (pintype "passive"))
      (node (ref "R5") (pin "7") (pinfunction "7_7") (pintype "passive"))
      (node (ref "R5") (pin "8") (pinfunction "8_8") (pintype "passive"))
      (node (ref "R6") (pin "1") (pinfunction "1_1") (pintype "passive"))
      (node (ref "R7") (pin "5") (pinfunction "5_5") (pintype "passive"))
      (node (ref "R7") (pin "6") (pinfunction "6_6") (pintype "passive"))
      (node (ref "R7") (pin "7") (pinfunction "7_7") (pintype "passive"))
      (node (ref "R7") (pin "8") (pinfunction "8_8") (pintype "passive"))
      (node (ref "R8") (pin "5") (pinfunction "5_5") (pintype "passive"))
      (node (ref "R8") (pin "6") (pinfunction "6_6") (pintype "passive"))
      (node (ref "R8") (pin "7") (pinfunction "7_7") (pintype "passive"))
      (node (ref "R8") (pin "8") (pinfunction "8_8") (pintype "passive"))
      (node (ref "S1") (pin "2") (pinfunction "2_2") (pintype "passive"))
      (node (ref "U1") (pin "23") (pinfunction "VSS_1_23") (pintype "passive"))
      (node (ref "U1") (pin "35") (pinfunction "VSS_2_35") (pintype "passive"))
      (node (ref "U1") (pin "47") (pinfunction "VSS_3_47") (pintype "passive"))
      (node (ref "U1") (pin "8") (pinfunction "VSSA_8") (pintype "passive"))
      (node (ref "U2") (pin "10") (pinfunction "GND_10") (pintype "passive"))
      (node (ref "U2") (pin "19") (pinfunction "~{OE}_19") (pintype "passive"))
      (node (ref "U3") (pin "10") (pinfunction "GND_10") (pintype "passive"))
      (node (ref "U3") (pin "19") (pinfunction "~{OE}_19") (pintype "passive"))
      (node (ref "U4") (pin "10") (pinfunction "GND_10") (pintype "passive"))
      (node (ref "U4") (pin "19") (pinfunction "~{OE}_19") (pintype "passive"))
      (node (ref "U5") (pin "1") (pinfunction "VSS_1") (pintype "passive"))
      (node (ref "U6") (pin "2") (pinfunction "GND_2") (pintype "power_in"))
      (node (ref "U7") (pin "15") (pinfunction "GND_15") (pintype "passive"))
      (node (ref "U8") (pin "4") (pinfunction "GND_4") (pintype "power_in"))
      (node (ref "U8") (pin "9") (pinfunction "GND_9") (pintype "power_in"))
    )
    (net (code "60") (name "Isen") (class "Default")
      (node (ref "R19") (pin "2") (pinfunction "2_2") (pintype "passive"))
      (node (ref "U1") (pin "14") (pinfunction "PA4/ADC123_IN4/DAC_OUT1/SPI1_NSS_14") (pintype "passive"))
      (node (ref "U6") (pin "1") (pinfunction "OUT_1") (pintype "power_in"))
    )
    (net (code "61") (name "Net-(C20-Pad1)") (class "Default")
      (node (ref "C20") (pin "1") (pinfunction "1_1") (pintype "passive"))
      (node (ref "R15") (pin "1") (pinfunction "1_1") (pintype "passive"))
    )
    (net (code "62") (name "Net-(D1-Pad1)") (class "Default")
      (node (ref "D1") (pin "1") (pinfunction "1_1") (pintype "passive"))
      (node (ref "R10") (pin "2") (pinfunction "2_2") (pintype "passive"))
    )
    (net (code "63") (name "Net-(D2-Pad1)") (class "Default")
      (node (ref "D2") (pin "1") (pinfunction "1_1") (pintype "passive"))
      (node (ref "R20") (pin "2") (pinfunction "2_2") (pintype "passive"))
    )
    (net (code "64") (name "Net-(U1-BOOT0)") (class "Default")
      (node (ref "R3") (pin "2") (pinfunction "2_2") (pintype "passive"))
      (node (ref "U1") (pin "44") (pinfunction "BOOT0_44") (pintype "passive"))
    )
    (net (code "65") (name "Net-(U1-OSC_IN)") (class "Default")
      (node (ref "C3") (pin "1") (pinfunction "1_1") (pintype "passive"))
      (node (ref "U1") (pin "5") (pinfunction "OSC_IN_5") (pintype "passive"))
      (node (ref "Y1") (pin "2") (pinfunction "2_2") (pintype "passive"))
    )
    (net (code "66") (name "Net-(U1-OSC_OUT)") (class "Default")
      (node (ref "C4") (pin "1") (pinfunction "1_1") (pintype "passive"))
      (node (ref "U1") (pin "6") (pinfunction "OSC_OUT_6") (pintype "passive"))
      (node (ref "Y1") (pin "1") (pinfunction "1_1") (pintype "passive"))
    )
    (net (code "67") (name "Net-(U1-PA1{slash}ADC123_IN1{slash}T5C2{slash}T2C2)") (class "Default")
      (node (ref "C1") (pin "2") (pinfunction "2_2") (pintype "passive"))
      (node (ref "R1") (pin "2") (pinfunction "2_2") (pintype "passive"))
      (node (ref "R2") (pin "1") (pinfunction "1_1") (pintype "passive"))
      (node (ref "U1") (pin "11") (pinfunction "PA1/ADC123_IN1/T5C2/T2C2_11") (pintype "passive"))
    )
    (net (code "68") (name "Net-(U1-PB2{slash}BOOT1)") (class "Default")
      (node (ref "R6") (pin "2") (pinfunction "2_2") (pintype "passive"))
      (node (ref "U1") (pin "20") (pinfunction "PB2/BOOT1_20") (pintype "passive"))
    )
    (net (code "69") (name "Net-(U6-IN+)") (class "Default")
      (node (ref "C16") (pin "1") (pinfunction "1_1") (pintype "passive"))
      (node (ref "R14") (pin "1") (pinfunction "1_1") (pintype "passive"))
      (node (ref "U6") (pin "3") (pinfunction "IN+_3") (pintype "power_in"))
    )
    (net (code "70") (name "Net-(U6-IN-)") (class "Default")
      (node (ref "C16") (pin "2") (pinfunction "2_2") (pintype "passive"))
      (node (ref "R13") (pin "1") (pinfunction "1_1") (pintype "passive"))
      (node (ref "U6") (pin "4") (pinfunction "IN-_4") (pintype "power_in"))
    )
    (net (code "71") (name "Net-(U7-C1+)") (class "Default")
      (node (ref "C18") (pin "2") (pinfunction "2_2") (pintype "passive"))
      (node (ref "U7") (pin "1") (pinfunction "C1+_1") (pintype "passive"))
    )
    (net (code "72") (name "Net-(U7-C1-)") (class "Default")
      (node (ref "C18") (pin "1") (pinfunction "1_1") (pintype "passive"))
      (node (ref "U7") (pin "3") (pinfunction "C1-_3") (pintype "passive"))
    )
    (net (code "73") (name "Net-(U7-C2+)") (class "Default")
      (node (ref "C23") (pin "2") (pinfunction "2_2") (pintype "passive"))
      (node (ref "U7") (pin "4") (pinfunction "C2+_4") (pintype "passive"))
    )
    (net (code "74") (name "Net-(U7-C2-)") (class "Default")
      (node (ref "C23") (pin "1") (pinfunction "1_1") (pintype "passive"))
      (node (ref "U7") (pin "5") (pinfunction "C2-_5") (pintype "passive"))
    )
    (net (code "75") (name "Net-(U7-Vs+)") (class "Default")
      (node (ref "C21") (pin "2") (pinfunction "2_2") (pintype "passive"))
      (node (ref "U7") (pin "2") (pinfunction "Vs+_2") (pintype "passive"))
    )
    (net (code "76") (name "Net-(U7-Vs-)") (class "Default")
      (node (ref "C25") (pin "2") (pinfunction "2_2") (pintype "passive"))
      (node (ref "U7") (pin "6") (pinfunction "Vs-_6") (pintype "passive"))
    )
    (net (code "77") (name "Net-(U8-BS)") (class "Default")
      (node (ref "C26") (pin "2") (pinfunction "2_2") (pintype "passive"))
      (node (ref "U8") (pin "1") (pinfunction "BS_1") (pintype "power_in"))
    )
    (net (code "78") (name "Net-(U8-COMP)") (class "Default")
      (node (ref "C17") (pin "2") (pinfunction "2_2") (pintype "passive"))
      (node (ref "C20") (pin "2") (pinfunction "2_2") (pintype "passive"))
      (node (ref "U8") (pin "6") (pinfunction "COMP_6") (pintype "power_in"))
    )
    (net (code "79") (name "Net-(U8-EN)") (class "Default")
      (node (ref "R16") (pin "1") (pinfunction "1_1") (pintype "passive"))
      (node (ref "U8") (pin "7") (pinfunction "EN_7") (pintype "power_in"))
    )
    (net (code "80") (name "Net-(U8-FB)") (class "Default")
      (node (ref "R17") (pin "1") (pinfunction "1_1") (pintype "passive"))
      (node (ref "R18") (pin "2") (pinfunction "2_2") (pintype "passive"))
      (node (ref "U8") (pin "5") (pinfunction "FB_5") (pintype "power_in"))
    )
    (net (code "81") (name "Net-(U8-SS)") (class "Default")
      (node (ref "C22") (pin "1") (pinfunction "1_1") (pintype "passive"))
      (node (ref "U8") (pin "8") (pinfunction "SS_8") (pintype "power_in"))
    )
    (net (code "82") (name "Net-(U8-SW)") (class "Default")
      (node (ref "C26") (pin "1") (pinfunction "1_1") (pintype "passive"))
      (node (ref "L1") (pin "1") (pinfunction "1_1") (pintype "passive"))
      (node (ref "U8") (pin "3") (pinfunction "SW_3") (pintype "power_in"))
    )
    (net (code "83") (name "VBAT") (class "Default")
      (node (ref "P2") (pin "2") (pinfunction "2_2") (pintype "passive"))
      (node (ref "R14") (pin "2") (pinfunction "2_2") (pintype "passive"))
    )
    (net (code "84") (name "unconnected-(R12-Pad2)") (class "Default")
      (node (ref "R12") (pin "2") (pinfunction "2_2") (pintype "passive+no_connect"))
    )
    (net (code "85") (name "unconnected-(U1-PA12{slash}CAN_Tx{slash}T1ETR{slash}USBDP-Pad33)") (class "Default")
      (node (ref "U1") (pin "33") (pinfunction "PA12/CAN_Tx/T1ETR/USBDP_33") (pintype "passive"))
    )
    (net (code "86") (name "unconnected-(U1-PC13-TAMPER-RTC-Pad2)") (class "Default")
      (node (ref "U1") (pin "2") (pinfunction "PC13-TAMPER-RTC_2") (pintype "passive"))
    )
    (net (code "87") (name "unconnected-(U1-PC14-OSC32_IN-Pad3)") (class "Default")
      (node (ref "U1") (pin "3") (pinfunction "PC14-OSC32_IN_3") (pintype "passive"))
    )
    (net (code "88") (name "unconnected-(U1-PC15-OSC32_OUT-Pad4)") (class "Default")
      (node (ref "U1") (pin "4") (pinfunction "PC15-OSC32_OUT_4") (pintype "passive"))
    )
    (net (code "89") (name "unconnected-(U4-A6-Pad8)") (class "Default")
      (node (ref "U4") (pin "8") (pinfunction "A6_8") (pintype "passive+no_connect"))
    )
    (net (code "90") (name "unconnected-(U4-B6-Pad12)") (class "Default")
      (node (ref "U4") (pin "12") (pinfunction "B6_12") (pintype "passive+no_connect"))
    )
    (net (code "91") (name "unconnected-(U7-R2I-Pad8)") (class "Default")
      (node (ref "U7") (pin "8") (pinfunction "R2I_8") (pintype "passive"))
    )
    (net (code "92") (name "unconnected-(U7-R2O-Pad9)") (class "Default")
      (node (ref "U7") (pin "9") (pinfunction "R2O_9") (pintype "passive"))
    )
    (net (code "93") (name "unconnected-(U7-T2I-Pad10)") (class "Default")
      (node (ref "U7") (pin "10") (pinfunction "T2I_10") (pintype "passive"))
    )
    (net (code "94") (name "unconnected-(U7-T2O-Pad7)") (class "Default")
      (node (ref "U7") (pin "7") (pinfunction "T2O_7") (pintype "passive"))
    )
  )
)
